# Voltage_Translator.net
KiCad netlist of a schematic drawn in Altium Designer
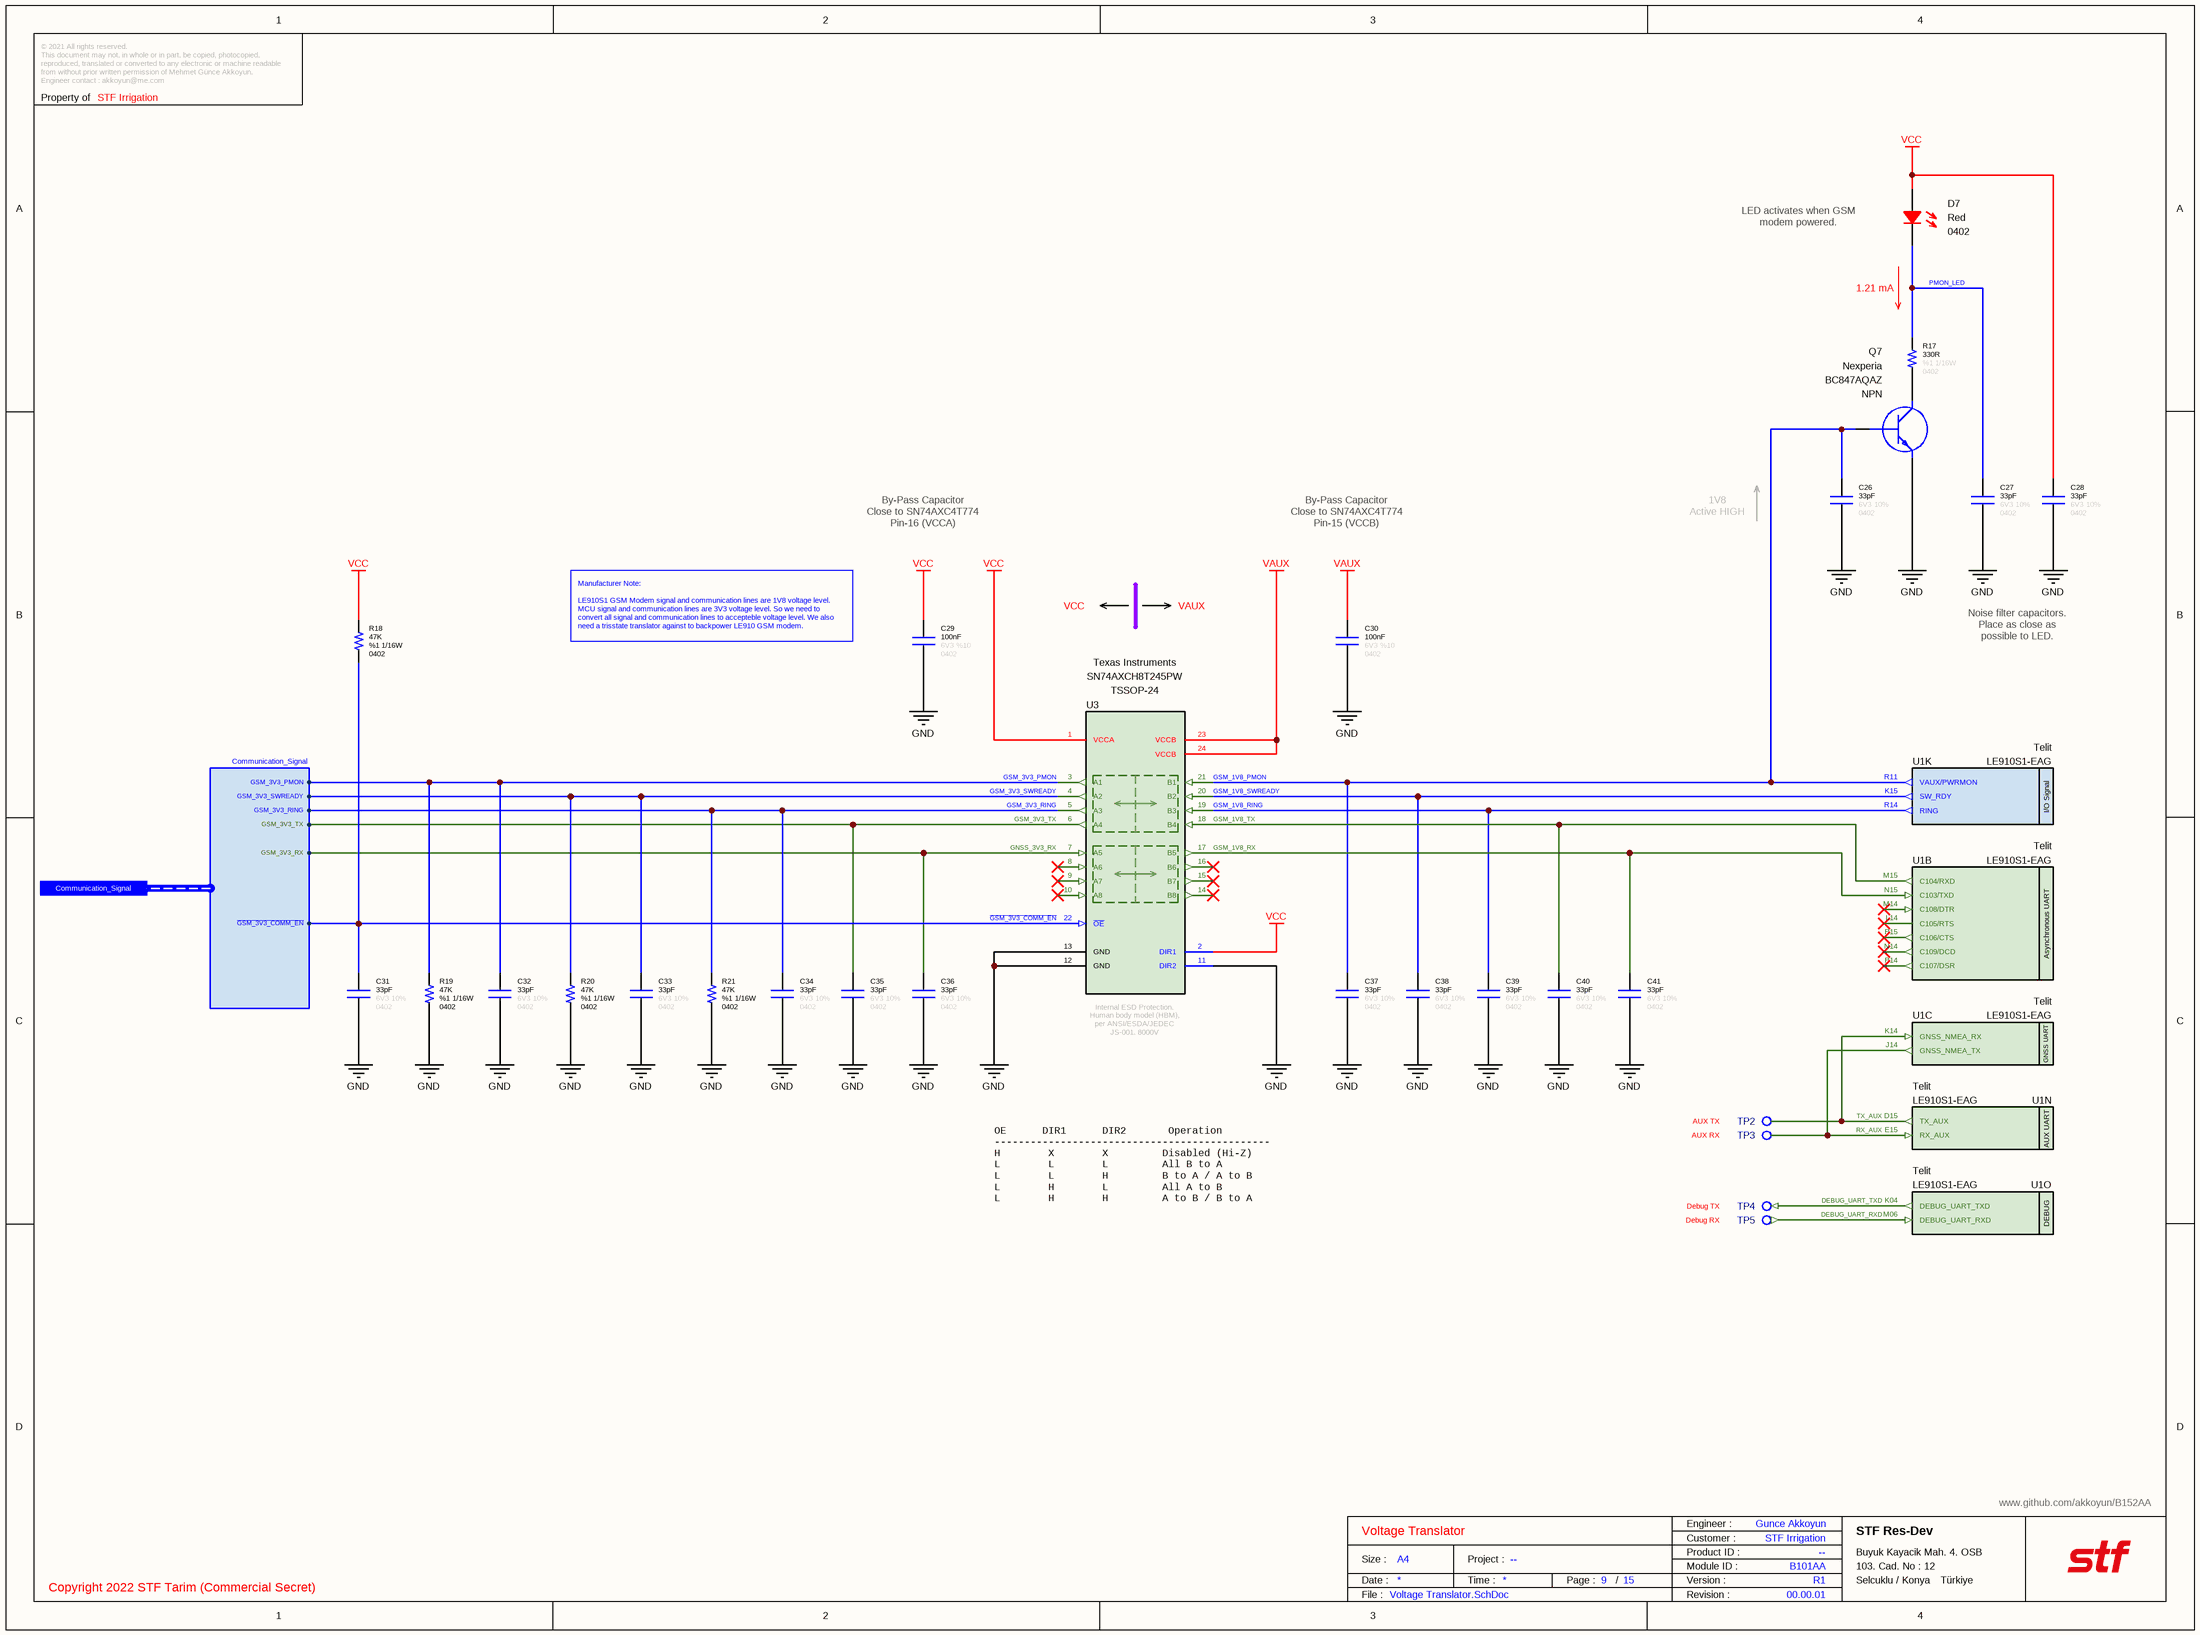
[diagram p0: Voltage Translator.SchDoc]

(export (version "E")
  (design (tool "Eeschema 10.0.6"))
  (components
    (comp (ref "C26")
      (value "33pF")
      (footprint "CAPACITOR_0402")
      (description "Capacitor - 33pF [0402] (Ceramic)")
      (fields
        (field (name "MANUFACTURER PART NUMBER") "C0402C330J9RACAUTO")
        (field (name "TOLERANCE") "10%")
        (field (name "CASE") "0402")
        (field (name "VOLTAGE") "6V3")
      )
      (libsource (lib "P101DA_Library") (part "Capacitor - 33pF [0402-6V3]"))
    )
    (comp (ref "C27")
      (value "33pF")
      (footprint "CAPACITOR_0402")
      (description "Capacitor - 33pF [0402] (Ceramic)")
      (fields
        (field (name "MANUFACTURER PART NUMBER") "C0402C330J9RACAUTO")
        (field (name "TOLERANCE") "10%")
        (field (name "CASE") "0402")
        (field (name "VOLTAGE") "6V3")
      )
      (libsource (lib "P101DA_Library") (part "Capacitor - 33pF [0402-6V3]"))
    )
    (comp (ref "C28")
      (value "33pF")
      (footprint "CAPACITOR_0402")
      (description "Capacitor - 33pF [0402] (Ceramic)")
      (fields
        (field (name "MANUFACTURER PART NUMBER") "C0402C330J9RACAUTO")
        (field (name "TOLERANCE") "10%")
        (field (name "CASE") "0402")
        (field (name "VOLTAGE") "6V3")
      )
      (libsource (lib "P101DA_Library") (part "Capacitor - 33pF [0402-6V3]"))
    )
    (comp (ref "C29")
      (value "100nF")
      (footprint "CAPACITOR_0402")
      (description "Capacitor - 100nF [0402-6V3] (Ceramic)")
      (fields
        (field (name "MANUFACTURER PART NUMBER") "04026D104KAT4A")
        (field (name "TOLERANCE") "%10")
        (field (name "VOLTAGE") "6V3")
        (field (name "CASE") "0402")
        (field (name "Comment") "Capacitor - 100nF [0402] (Ceramic)")
      )
      (libsource (lib "P101DA_Library") (part "Capacitor - 100nF [0402-6V3]"))
    )
    (comp (ref "C30")
      (value "100nF")
      (footprint "CAPACITOR_0402")
      (description "Capacitor - 100nF [0402-6V3] (Ceramic)")
      (fields
        (field (name "MANUFACTURER PART NUMBER") "04026D104KAT4A")
        (field (name "TOLERANCE") "%10")
        (field (name "VOLTAGE") "6V3")
        (field (name "CASE") "0402")
        (field (name "Comment") "Capacitor - 100nF [0402] (Ceramic)")
      )
      (libsource (lib "P101DA_Library") (part "Capacitor - 100nF [0402-6V3]"))
    )
    (comp (ref "C31")
      (value "33pF")
      (footprint "CAPACITOR_0402")
      (description "Capacitor - 33pF [0402] (Ceramic)")
      (fields
        (field (name "MANUFACTURER PART NUMBER") "C0402C330J9RACAUTO")
        (field (name "TOLERANCE") "10%")
        (field (name "CASE") "0402")
        (field (name "VOLTAGE") "6V3")
      )
      (libsource (lib "P101DA_Library") (part "Capacitor - 33pF [0402-6V3]"))
    )
    (comp (ref "C32")
      (value "33pF")
      (footprint "CAPACITOR_0402")
      (description "Capacitor - 33pF [0402] (Ceramic)")
      (fields
        (field (name "MANUFACTURER PART NUMBER") "C0402C330J9RACAUTO")
        (field (name "TOLERANCE") "10%")
        (field (name "CASE") "0402")
        (field (name "VOLTAGE") "6V3")
      )
      (libsource (lib "P101DA_Library") (part "Capacitor - 33pF [0402-6V3]"))
    )
    (comp (ref "C33")
      (value "33pF")
      (footprint "CAPACITOR_0402")
      (description "Capacitor - 33pF [0402] (Ceramic)")
      (fields
        (field (name "MANUFACTURER PART NUMBER") "C0402C330J9RACAUTO")
        (field (name "TOLERANCE") "10%")
        (field (name "CASE") "0402")
        (field (name "VOLTAGE") "6V3")
      )
      (libsource (lib "P101DA_Library") (part "Capacitor - 33pF [0402-6V3]"))
    )
    (comp (ref "C34")
      (value "33pF")
      (footprint "CAPACITOR_0402")
      (description "Capacitor - 33pF [0402] (Ceramic)")
      (fields
        (field (name "MANUFACTURER PART NUMBER") "C0402C330J9RACAUTO")
        (field (name "TOLERANCE") "10%")
        (field (name "CASE") "0402")
        (field (name "VOLTAGE") "6V3")
      )
      (libsource (lib "P101DA_Library") (part "Capacitor - 33pF [0402-6V3]"))
    )
    (comp (ref "C35")
      (value "33pF")
      (footprint "CAPACITOR_0402")
      (description "Capacitor - 33pF [0402] (Ceramic)")
      (fields
        (field (name "MANUFACTURER PART NUMBER") "C0402C330J9RACAUTO")
        (field (name "TOLERANCE") "10%")
        (field (name "CASE") "0402")
        (field (name "VOLTAGE") "6V3")
      )
      (libsource (lib "P101DA_Library") (part "Capacitor - 33pF [0402-6V3]"))
    )
    (comp (ref "C36")
      (value "33pF")
      (footprint "CAPACITOR_0402")
      (description "Capacitor - 33pF [0402] (Ceramic)")
      (fields
        (field (name "MANUFACTURER PART NUMBER") "C0402C330J9RACAUTO")
        (field (name "TOLERANCE") "10%")
        (field (name "CASE") "0402")
        (field (name "VOLTAGE") "6V3")
      )
      (libsource (lib "P101DA_Library") (part "Capacitor - 33pF [0402-6V3]"))
    )
    (comp (ref "C37")
      (value "33pF")
      (footprint "CAPACITOR_0402")
      (description "Capacitor - 33pF [0402] (Ceramic)")
      (fields
        (field (name "MANUFACTURER PART NUMBER") "C0402C330J9RACAUTO")
        (field (name "TOLERANCE") "10%")
        (field (name "CASE") "0402")
        (field (name "VOLTAGE") "6V3")
      )
      (libsource (lib "P101DA_Library") (part "Capacitor - 33pF [0402-6V3]"))
    )
    (comp (ref "C38")
      (value "33pF")
      (footprint "CAPACITOR_0402")
      (description "Capacitor - 33pF [0402] (Ceramic)")
      (fields
        (field (name "MANUFACTURER PART NUMBER") "C0402C330J9RACAUTO")
        (field (name "TOLERANCE") "10%")
        (field (name "CASE") "0402")
        (field (name "VOLTAGE") "6V3")
      )
      (libsource (lib "P101DA_Library") (part "Capacitor - 33pF [0402-6V3]"))
    )
    (comp (ref "C39")
      (value "33pF")
      (footprint "CAPACITOR_0402")
      (description "Capacitor - 33pF [0402] (Ceramic)")
      (fields
        (field (name "MANUFACTURER PART NUMBER") "C0402C330J9RACAUTO")
        (field (name "TOLERANCE") "10%")
        (field (name "CASE") "0402")
        (field (name "VOLTAGE") "6V3")
      )
      (libsource (lib "P101DA_Library") (part "Capacitor - 33pF [0402-6V3]"))
    )
    (comp (ref "C40")
      (value "33pF")
      (footprint "CAPACITOR_0402")
      (description "Capacitor - 33pF [0402] (Ceramic)")
      (fields
        (field (name "MANUFACTURER PART NUMBER") "C0402C330J9RACAUTO")
        (field (name "TOLERANCE") "10%")
        (field (name "CASE") "0402")
        (field (name "VOLTAGE") "6V3")
      )
      (libsource (lib "P101DA_Library") (part "Capacitor - 33pF [0402-6V3]"))
    )
    (comp (ref "C41")
      (value "33pF")
      (footprint "CAPACITOR_0402")
      (description "Capacitor - 33pF [0402] (Ceramic)")
      (fields
        (field (name "MANUFACTURER PART NUMBER") "C0402C330J9RACAUTO")
        (field (name "TOLERANCE") "10%")
        (field (name "CASE") "0402")
        (field (name "VOLTAGE") "6V3")
      )
      (libsource (lib "P101DA_Library") (part "Capacitor - 33pF [0402-6V3]"))
    )
    (comp (ref "D7")
      (value "SMD LED (Red)")
      (footprint "LED_0402")
      (description "Standard LEDs - SMD MINI-MOLD ULTRA COMPACT RED")
      (fields
        (field (name "MANUFACTURER PART NUMBER") "SML-P12VTT86R")
        (field (name "CASE") "0402")
        (field (name "COLOR") "Red")
      )
      (libsource (lib "P101DA_Library") (part "Diode - LED (0402-Red)"))
    )
    (comp (ref "Q7")
      (value "BC847AQAZ")
      (footprint "SOT1215")
      (description "Bipolar NPN Transistors")
      (fields
        (field (name "MANUFACTURER NAME") "Nexperia")
        (field (name "MANUFACTURER PART NUMBER") "BC847AQAZ")
        (field (name "POLARITY") "NPN")
      )
      (libsource (lib "P101DA_Library") (part "Transistor - BC847"))
    )
    (comp (ref "R17")
      (value "330R")
      (footprint "RESISTOR_0402")
      (description "Thick Film Resistors - SMD 1/16 W 330 Ohm 1%")
      (fields
        (field (name "MANUFACTURER PART NUMBER") "CRCW0402330RFKED")
        (field (name "CASE") "0402")
        (field (name "TOLERANCE") "%1")
        (field (name "POWER") "1/16W")
        (field (name "Comment") "330R - 0402 - %1 - 1/16W")
      )
      (libsource (lib "P101DA_Library") (part "Resistor - 330R [0402]"))
    )
    (comp (ref "R18")
      (value "47K")
      (footprint "RESISTOR_0402")
      (description "Thick Film Resistors - SMD 1/16 W 47 KOhm 1%")
      (fields
        (field (name "MANUFACTURER PART NUMBER") "CRCW040247K0FKED")
        (field (name "TOLERANCE") "%1")
        (field (name "CASE") "0402")
        (field (name "POWER") "1/16W")
        (field (name "Comment") "47K - 0402 - %1 - 1/16W")
      )
      (libsource (lib "P101DA_Library") (part "Resistor - 47K [0402]"))
    )
    (comp (ref "R19")
      (value "47K")
      (footprint "RESISTOR_0402")
      (description "Thick Film Resistors - SMD 1/16 W 47 KOhm 1%")
      (fields
        (field (name "MANUFACTURER PART NUMBER") "CRCW040247K0FKED")
        (field (name "TOLERANCE") "%1")
        (field (name "CASE") "0402")
        (field (name "POWER") "1/16W")
        (field (name "Comment") "47K - 0402 - %1 - 1/16W")
      )
      (libsource (lib "P101DA_Library") (part "Resistor - 47K [0402]"))
    )
    (comp (ref "R20")
      (value "47K")
      (footprint "RESISTOR_0402")
      (description "Thick Film Resistors - SMD 1/16 W 47 KOhm 1%")
      (fields
        (field (name "MANUFACTURER PART NUMBER") "CRCW040247K0FKED")
        (field (name "TOLERANCE") "%1")
        (field (name "CASE") "0402")
        (field (name "POWER") "1/16W")
        (field (name "Comment") "47K - 0402 - %1 - 1/16W")
      )
      (libsource (lib "P101DA_Library") (part "Resistor - 47K [0402]"))
    )
    (comp (ref "R21")
      (value "47K")
      (footprint "RESISTOR_0402")
      (description "Thick Film Resistors - SMD 1/16 W 47 KOhm 1%")
      (fields
        (field (name "MANUFACTURER PART NUMBER") "CRCW040247K0FKED")
        (field (name "TOLERANCE") "%1")
        (field (name "CASE") "0402")
        (field (name "POWER") "1/16W")
        (field (name "Comment") "47K - 0402 - %1 - 1/16W")
      )
      (libsource (lib "P101DA_Library") (part "Resistor - 47K [0402]"))
    )
    (comp (ref "TP2")
      (value "~")
      (footprint "Test_Pad - Hole")
      (description "Test Point")
      (fields (field (name "NAME") "AUX TX"))
      (libsource (lib "P101DA_Library") (part "Test Point"))
    )
    (comp (ref "TP3")
      (value "~")
      (footprint "Test_Pad - Hole")
      (description "Test Point")
      (fields (field (name "NAME") "AUX RX"))
      (libsource (lib "P101DA_Library") (part "Test Point"))
    )
    (comp (ref "TP4")
      (value "~")
      (footprint "Test_Pad - Hole")
      (description "Test Point")
      (fields (field (name "NAME") "Debug TX"))
      (libsource (lib "P101DA_Library") (part "Test Point"))
    )
    (comp (ref "TP5")
      (value "~")
      (footprint "Test_Pad - Hole")
      (description "Test Point")
      (fields (field (name "NAME") "Debug RX"))
      (libsource (lib "P101DA_Library") (part "Test Point"))
    )
    (comp (ref "U1")
      (value "LE910S1-EAG LTE GSM Module")
      (footprint "LE910 GSM Modem")
      (description "Telit LE910S1-EAG GPRS/GNSS Module")
      (fields
        (field (name "MANUFACTURER PART NUMBER") "LE910S1-EAG")
        (field (name "MANUFACTURER NAME") "Telit")
      )
      (libsource (lib "P101DA_Library") (part "IC - LE910S1-EAG"))
    )
    (comp (ref "U3")
      (value "SN74AXCH8T245PW")
      (footprint "TSSOP-24")
      (description "Translation - Voltage Levels 8-Bit Dual-Supply Bus Transceiver 24-TSSOP -40 to 125")
      (fields
        (field (name "MANUFACTURER NAME") "Texas Instruments")
        (field (name "MANUFACTURER PART NUMBER") "SN74AXCH8T245PW")
        (field (name "CASE") "TSSOP-24")
      )
      (libsource (lib "P101DA_Library") (part "IC - SN74AXCH8T245PW"))
    )
  )
  (nets
    (net (code "2") (name "/DEBUG_UART_RXD") (class "Default")
      (node (ref "TP5") (pin "1") (pinfunction "1_1") (pintype "passive"))
      (node (ref "U1") (pin "M06") (pinfunction "DEBUG_UART_RXD_M06") (pintype "input"))
    )
    (net (code "3") (name "/DEBUG_UART_TXD") (class "Default")
      (node (ref "TP4") (pin "1") (pinfunction "1_1") (pintype "passive"))
      (node (ref "U1") (pin "K04") (pinfunction "DEBUG_UART_TXD_K04") (pintype "output"))
    )
    (net (code "4") (name "/GNSS_3V3_RX") (class "Default")
      (node (ref "C36") (pin "2") (pinfunction "2_2") (pintype "passive"))
      (node (ref "U3") (pin "7") (pinfunction "A5_7") (pintype "input"))
    )
    (net (code "5") (name "/GSM_1V8_PMON") (class "Default")
      (node (ref "C26") (pin "2") (pinfunction "2_2") (pintype "passive"))
      (node (ref "C37") (pin "2") (pinfunction "2_2") (pintype "passive"))
      (node (ref "Q7") (pin "1") (pinfunction "B_1") (pintype "passive"))
      (node (ref "U1") (pin "R11") (pinfunction "VAUX/PWRMON_R11") (pintype "output"))
      (node (ref "U3") (pin "21") (pinfunction "B1_21") (pintype "input"))
    )
    (net (code "6") (name "/GSM_1V8_RING") (class "Default")
      (node (ref "C39") (pin "2") (pinfunction "2_2") (pintype "passive"))
      (node (ref "U1") (pin "R14") (pinfunction "RING_R14") (pintype "output"))
      (node (ref "U3") (pin "19") (pinfunction "B3_19") (pintype "input"))
    )
    (net (code "7") (name "/GSM_1V8_RX") (class "Default")
      (node (ref "C41") (pin "2") (pinfunction "2_2") (pintype "passive"))
      (node (ref "U1") (pin "N15") (pinfunction "C103/TXD_N15") (pintype "input"))
      (node (ref "U3") (pin "17") (pinfunction "B5_17") (pintype "output"))
    )
    (net (code "8") (name "/GSM_1V8_SWREADY") (class "Default")
      (node (ref "C38") (pin "2") (pinfunction "2_2") (pintype "passive"))
      (node (ref "U1") (pin "K15") (pinfunction "SW_RDY_K15") (pintype "output"))
      (node (ref "U3") (pin "20") (pinfunction "B2_20") (pintype "input"))
    )
    (net (code "9") (name "/GSM_1V8_TX") (class "Default")
      (node (ref "C40") (pin "2") (pinfunction "2_2") (pintype "passive"))
      (node (ref "U1") (pin "M15") (pinfunction "C104/RXD_M15") (pintype "output"))
      (node (ref "U3") (pin "18") (pinfunction "B4_18") (pintype "input"))
    )
    (net (code "10") (name "/GSM_3V3_PMON") (class "Default")
      (node (ref "C32") (pin "2") (pinfunction "2_2") (pintype "passive"))
      (node (ref "R19") (pin "2") (pinfunction "2_2") (pintype "passive"))
      (node (ref "U3") (pin "3") (pinfunction "A1_3") (pintype "output"))
    )
    (net (code "11") (name "/GSM_3V3_RING") (class "Default")
      (node (ref "C34") (pin "2") (pinfunction "2_2") (pintype "passive"))
      (node (ref "R21") (pin "2") (pinfunction "2_2") (pintype "passive"))
      (node (ref "U3") (pin "5") (pinfunction "A3_5") (pintype "output"))
    )
    (net (code "12") (name "/GSM_3V3_SWREADY") (class "Default")
      (node (ref "C33") (pin "2") (pinfunction "2_2") (pintype "passive"))
      (node (ref "R20") (pin "2") (pinfunction "2_2") (pintype "passive"))
      (node (ref "U3") (pin "4") (pinfunction "A2_4") (pintype "output"))
    )
    (net (code "13") (name "/GSM_3V3_TX") (class "Default")
      (node (ref "C35") (pin "2") (pinfunction "2_2") (pintype "passive"))
      (node (ref "U3") (pin "6") (pinfunction "A4_6") (pintype "output"))
    )
    (net (code "14") (name "/PMON_LED") (class "Default")
      (node (ref "C27") (pin "2") (pinfunction "2_2") (pintype "passive"))
      (node (ref "D7") (pin "1") (pinfunction "1_1") (pintype "passive"))
      (node (ref "R17") (pin "2") (pinfunction "2_2") (pintype "passive"))
    )
    (net (code "15") (name "/RX_AUX") (class "Default")
      (node (ref "TP3") (pin "1") (pinfunction "1_1") (pintype "passive"))
      (node (ref "U1") (pin "E15") (pinfunction "RX_AUX_E15") (pintype "input"))
      (node (ref "U1") (pin "J14") (pinfunction "GNSS_NMEA_TX_J14") (pintype "output"))
    )
    (net (code "16") (name "/TX_AUX") (class "Default")
      (node (ref "TP2") (pin "1") (pinfunction "1_1") (pintype "passive"))
      (node (ref "U1") (pin "D15") (pinfunction "TX_AUX_D15") (pintype "output"))
      (node (ref "U1") (pin "K14") (pinfunction "GNSS_NMEA_RX_K14") (pintype "input"))
    )
    (net (code "18") (name "/~{GSM_3V3_COMM_EN}") (class "Default")
      (node (ref "C31") (pin "2") (pinfunction "2_2") (pintype "passive"))
      (node (ref "R18") (pin "1") (pinfunction "1_1") (pintype "passive"))
      (node (ref "U3") (pin "22") (pinfunction "~{OE}_22") (pintype "input"))
    )
    (net (code "19") (name "GND") (class "Default")
      (node (ref "C26") (pin "1") (pinfunction "1_1") (pintype "passive"))
      (node (ref "C27") (pin "1") (pinfunction "1_1") (pintype "passive"))
      (node (ref "C28") (pin "1") (pinfunction "1_1") (pintype "passive"))
      (node (ref "C29") (pin "1") (pinfunction "1_1") (pintype "passive"))
      (node (ref "C30") (pin "1") (pinfunction "1_1") (pintype "passive"))
      (node (ref "C31") (pin "1") (pinfunction "1_1") (pintype "passive"))
      (node (ref "C32") (pin "1") (pinfunction "1_1") (pintype "passive"))
      (node (ref "C33") (pin "1") (pinfunction "1_1") (pintype "passive"))
      (node (ref "C34") (pin "1") (pinfunction "1_1") (pintype "passive"))
      (node (ref "C35") (pin "1") (pinfunction "1_1") (pintype "passive"))
      (node (ref "C36") (pin "1") (pinfunction "1_1") (pintype "passive"))
      (node (ref "C37") (pin "1") (pinfunction "1_1") (pintype "passive"))
      (node (ref "C38") (pin "1") (pinfunction "1_1") (pintype "passive"))
      (node (ref "C39") (pin "1") (pinfunction "1_1") (pintype "passive"))
      (node (ref "C40") (pin "1") (pinfunction "1_1") (pintype "passive"))
      (node (ref "C41") (pin "1") (pinfunction "1_1") (pintype "passive"))
      (node (ref "Q7") (pin "2") (pinfunction "E_2") (pintype "passive"))
      (node (ref "R19") (pin "1") (pinfunction "1_1") (pintype "passive"))
      (node (ref "R20") (pin "1") (pinfunction "1_1") (pintype "passive"))
      (node (ref "R21") (pin "1") (pinfunction "1_1") (pintype "passive"))
      (node (ref "U3") (pin "11") (pinfunction "DIR2_11") (pintype "passive"))
      (node (ref "U3") (pin "12") (pinfunction "GND_12") (pintype "power_in"))
      (node (ref "U3") (pin "13") (pinfunction "GND_13") (pintype "power_in"))
    )
    (net (code "20") (name "Net-(Q7-C)") (class "Default")
      (node (ref "Q7") (pin "3") (pinfunction "C_3") (pintype "passive"))
      (node (ref "R17") (pin "1") (pinfunction "1_1") (pintype "passive"))
    )
    (net (code "21") (name "VAUX") (class "Default")
      (node (ref "C30") (pin "2") (pinfunction "2_2") (pintype "passive"))
      (node (ref "U3") (pin "23") (pinfunction "VCCB_23") (pintype "power_in"))
      (node (ref "U3") (pin "24") (pinfunction "VCCB_24") (pintype "power_in"))
    )
    (net (code "22") (name "VCC") (class "Default")
      (node (ref "C28") (pin "2") (pinfunction "2_2") (pintype "passive"))
      (node (ref "C29") (pin "2") (pinfunction "2_2") (pintype "passive"))
      (node (ref "D7") (pin "2") (pinfunction "2_2") (pintype "passive"))
      (node (ref "R18") (pin "2") (pinfunction "2_2") (pintype "passive"))
      (node (ref "U3") (pin "1") (pinfunction "VCCA_1") (pintype "power_in"))
      (node (ref "U3") (pin "2") (pinfunction "DIR1_2") (pintype "passive"))
    )
    (net (code "23") (name "unconnected-(U1B-C105{slash}RTS-PadL14)") (class "Default")
      (node (ref "U1") (pin "L14") (pinfunction "C105/RTS_L14") (pintype "open_collector+no_connect"))
    )
    (net (code "24") (name "unconnected-(U1B-C106{slash}CTS-PadP15)") (class "Default")
      (node (ref "U1") (pin "P15") (pinfunction "C106/CTS_P15") (pintype "output+no_connect"))
    )
    (net (code "25") (name "unconnected-(U1B-C107{slash}DSR-PadP14)") (class "Default")
      (node (ref "U1") (pin "P14") (pinfunction "C107/DSR_P14") (pintype "output+no_connect"))
    )
    (net (code "26") (name "unconnected-(U1B-C108{slash}DTR-PadM14)") (class "Default")
      (node (ref "U1") (pin "M14") (pinfunction "C108/DTR_M14") (pintype "input+no_connect"))
    )
    (net (code "27") (name "unconnected-(U1B-C109{slash}DCD-PadN14)") (class "Default")
      (node (ref "U1") (pin "N14") (pinfunction "C109/DCD_N14") (pintype "output+no_connect"))
    )
    (net (code "28") (name "unconnected-(U3-A6-Pad8)") (class "Default")
      (node (ref "U3") (pin "8") (pinfunction "A6_8") (pintype "input+no_connect"))
    )
    (net (code "29") (name "unconnected-(U3-A7-Pad9)") (class "Default")
      (node (ref "U3") (pin "9") (pinfunction "A7_9") (pintype "input+no_connect"))
    )
    (net (code "30") (name "unconnected-(U3-A8-Pad10)") (class "Default")
      (node (ref "U3") (pin "10") (pinfunction "A8_10") (pintype "input+no_connect"))
    )
    (net (code "31") (name "unconnected-(U3-B6-Pad16)") (class "Default")
      (node (ref "U3") (pin "16") (pinfunction "B6_16") (pintype "output+no_connect"))
    )
    (net (code "32") (name "unconnected-(U3-B7-Pad15)") (class "Default")
      (node (ref "U3") (pin "15") (pinfunction "B7_15") (pintype "output+no_connect"))
    )
    (net (code "33") (name "unconnected-(U3-B8-Pad14)") (class "Default")
      (node (ref "U3") (pin "14") (pinfunction "B8_14") (pintype "output+no_connect"))
    )
  )
)
